# ArduinoNano_LearningBot_4-21-18.net
KiCad netlist of a schematic drawn in EAGLE
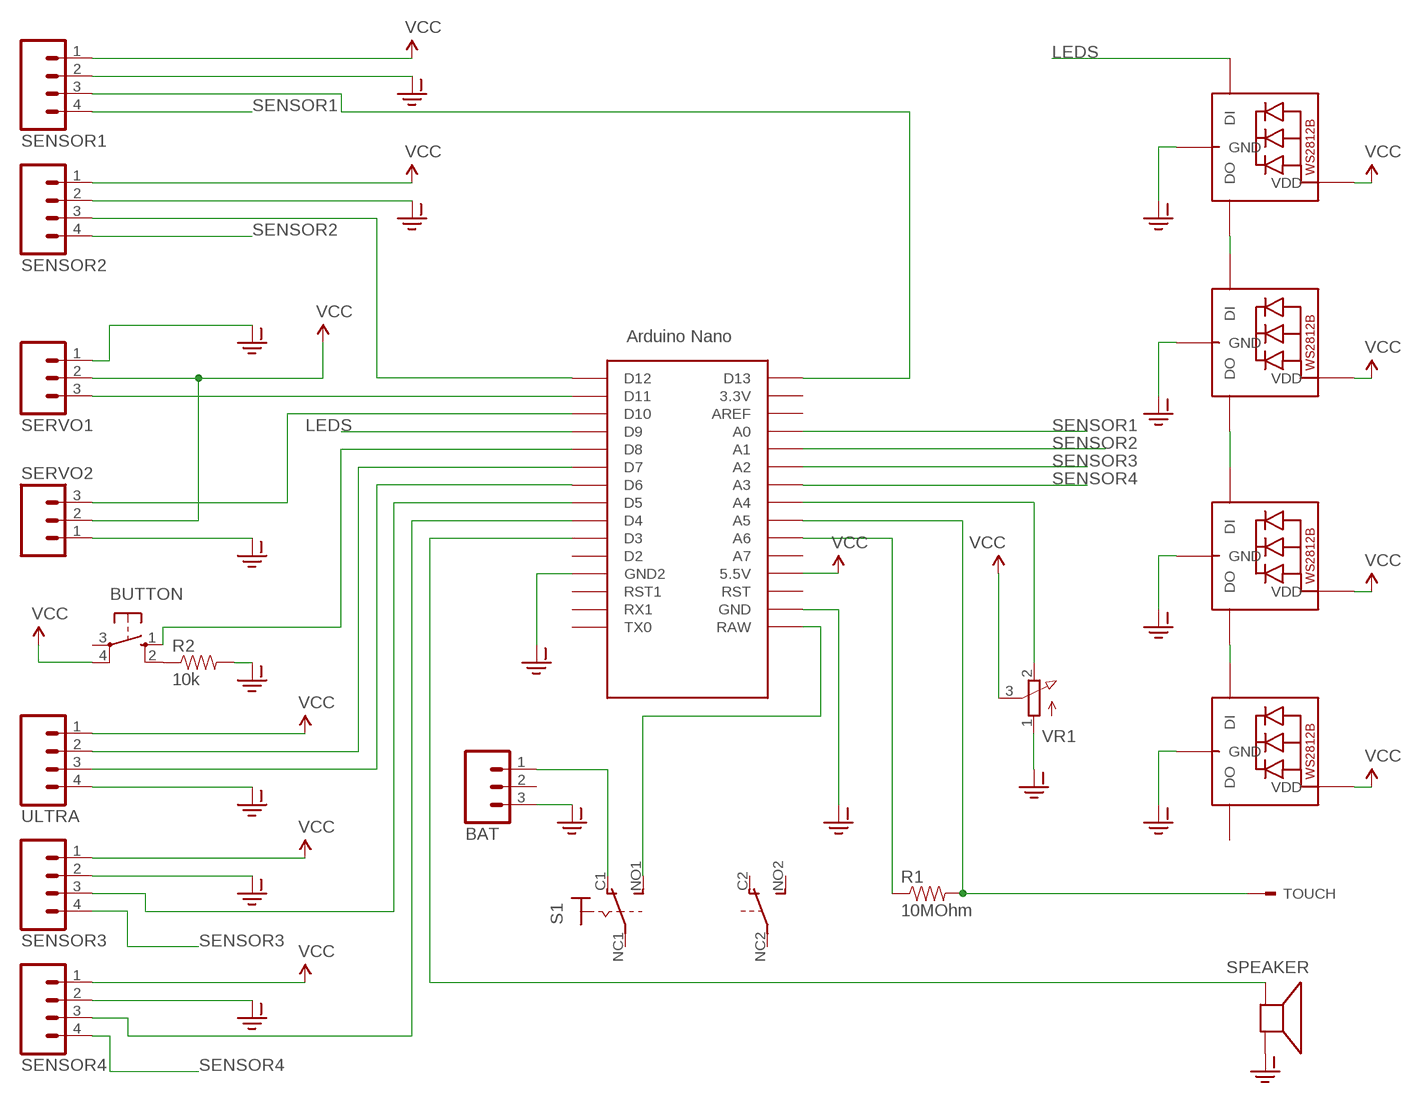
[diagram p0: schematic, sheet 1]

(export (version "E")
  (design (tool "Eeschema 10.0.6"))
  (components
    (comp (ref "BAT")
      (value "M03POLAR")
      (footprint "eagle-import:MOLEX-1X3")
      (libsource (lib "eagle-import") (part "M03POLAR"))
    )
    (comp (ref "BUTTON")
      (value "10-XX")
      (footprint "eagle-import:B3F-10XX")
      (fields (field (name "MPN") "B3F-1000"))
      (libsource (lib "eagle-import") (part "10-XX"))
    )
    (comp (ref "LED1")
      (value "WS2812B5050")
      (footprint "eagle-import:WS2812B")
      (libsource (lib "eagle-import") (part "WS2812B5050"))
    )
    (comp (ref "LED2")
      (value "WS2812B5050")
      (footprint "eagle-import:WS2812B")
      (libsource (lib "eagle-import") (part "WS2812B5050"))
    )
    (comp (ref "LED3")
      (value "WS2812B5050")
      (footprint "eagle-import:WS2812B")
      (libsource (lib "eagle-import") (part "WS2812B5050"))
    )
    (comp (ref "LED4")
      (value "WS2812B5050")
      (footprint "eagle-import:WS2812B")
      (libsource (lib "eagle-import") (part "WS2812B5050"))
    )
    (comp (ref "R1")
      (value "10MOhm")
      (footprint "eagle-import:AXIAL-0.4")
      (libsource (lib "eagle-import") (part "RESISTORPTH-1/4W"))
    )
    (comp (ref "R2")
      (value "10k")
      (footprint "eagle-import:AXIAL-0.4")
      (libsource (lib "eagle-import") (part "RESISTORPTH-1/4W"))
    )
    (comp (ref "S1")
      (value "SWITCH_320-938")
      (footprint "eagle-import:PS22F03")
      (libsource (lib "eagle-import") (part "SWITCH_320-938"))
    )
    (comp (ref "SENSOR1")
      (value "M04LOCK")
      (footprint "eagle-import:1X04_LOCK")
      (libsource (lib "eagle-import") (part "M04LOCK"))
    )
    (comp (ref "SENSOR2")
      (value "M04LOCK")
      (footprint "eagle-import:1X04_LOCK")
      (libsource (lib "eagle-import") (part "M04LOCK"))
    )
    (comp (ref "SENSOR3")
      (value "M04LOCK")
      (footprint "eagle-import:1X04_LOCK")
      (libsource (lib "eagle-import") (part "M04LOCK"))
    )
    (comp (ref "SENSOR4")
      (value "M04LOCK")
      (footprint "eagle-import:1X04_LOCK")
      (libsource (lib "eagle-import") (part "M04LOCK"))
    )
    (comp (ref "SERVO1")
      (value "M03LOCK")
      (footprint "eagle-import:1X03_LOCK")
      (libsource (lib "eagle-import") (part "SparkFun-Connectors_513_M03LOCK"))
    )
    (comp (ref "SERVO2")
      (value "M03LOCK")
      (footprint "eagle-import:1X03_LOCK")
      (libsource (lib "eagle-import") (part "SparkFun-Connectors_513_M03LOCK"))
    )
    (comp (ref "SPEAKER")
      (value "SPEAKER/AL60P")
      (footprint "eagle-import:AL60P")
      (libsource (lib "eagle-import") (part "SPEAKER/AL60P"))
    )
    (comp (ref "TOUCH")
      (value "TOUCHSENSOR")
      (footprint "eagle-import:TOUCH1")
      (libsource (lib "eagle-import") (part "TOUCHSENSOR"))
    )
    (comp (ref "U$1")
      (value "ARDUINO-CLONE_NANO")
      (footprint "eagle-import:ARDUINO-CLONE_NANO")
      (libsource (lib "eagle-import") (part "ARDUINO-CLONE_NANO"))
    )
    (comp (ref "ULTRA")
      (value "M04LOCK")
      (footprint "eagle-import:1X04_LOCK")
      (libsource (lib "eagle-import") (part "M04LOCK"))
    )
    (comp (ref "VR1")
      (value "3RP/1610N-VERTICAL")
      (footprint "eagle-import:3RP_1610N-VERTICAL")
      (libsource (lib "eagle-import") (part "3RP/1610N-VERTICAL"))
    )
  )
  (nets
    (net (code "1") (name "/LEDS") (class "Default")
      (node (ref "LED1") (pin "4-DIN") (pinfunction "DI_4-DIN") (pintype "input"))
      (node (ref "U$1") (pin "D9") (pinfunction "D9_D9") (pintype "bidirectional"))
    )
    (net (code "2") (name "/SENSOR1") (class "Default")
      (node (ref "SENSOR1") (pin "4") (pinfunction "4_4") (pintype "passive"))
      (node (ref "U$1") (pin "A0") (pinfunction "A0_A0") (pintype "bidirectional"))
    )
    (net (code "3") (name "/SENSOR2") (class "Default")
      (node (ref "SENSOR2") (pin "4") (pinfunction "4_4") (pintype "passive"))
      (node (ref "U$1") (pin "A1") (pinfunction "A1_A1") (pintype "bidirectional"))
    )
    (net (code "4") (name "/SENSOR3") (class "Default")
      (node (ref "SENSOR3") (pin "4") (pinfunction "4_4") (pintype "passive"))
      (node (ref "U$1") (pin "A2") (pinfunction "A2_A2") (pintype "bidirectional"))
    )
    (net (code "5") (name "/SENSOR4") (class "Default")
      (node (ref "SENSOR4") (pin "4") (pinfunction "4_4") (pintype "passive"))
      (node (ref "U$1") (pin "A3") (pinfunction "A3_A3") (pintype "bidirectional"))
    )
    (net (code "6") (name "GND-ISO") (class "Default")
      (node (ref "BAT") (pin "3") (pinfunction "3_3") (pintype "passive"))
      (node (ref "LED1") (pin "3-GND") (pinfunction "GND_3-GND") (pintype "power_in"))
      (node (ref "LED2") (pin "3-GND") (pinfunction "GND_3-GND") (pintype "power_in"))
      (node (ref "LED3") (pin "3-GND") (pinfunction "GND_3-GND") (pintype "power_in"))
      (node (ref "LED4") (pin "3-GND") (pinfunction "GND_3-GND") (pintype "power_in"))
      (node (ref "R2") (pin "P$2") (pinfunction "2_P$2") (pintype "passive"))
      (node (ref "SENSOR1") (pin "2") (pinfunction "2_2") (pintype "passive"))
      (node (ref "SENSOR2") (pin "2") (pinfunction "2_2") (pintype "passive"))
      (node (ref "SENSOR3") (pin "2") (pinfunction "2_2") (pintype "passive"))
      (node (ref "SENSOR4") (pin "2") (pinfunction "2_2") (pintype "passive"))
      (node (ref "SERVO1") (pin "1") (pinfunction "1_1") (pintype "passive"))
      (node (ref "SERVO2") (pin "1") (pinfunction "1_1") (pintype "passive"))
      (node (ref "SPEAKER") (pin "1") (pinfunction "+_1") (pintype "passive"))
      (node (ref "U$1") (pin "GND") (pinfunction "GND_GND") (pintype "bidirectional"))
      (node (ref "U$1") (pin "GND1") (pinfunction "GND2_GND1") (pintype "bidirectional"))
      (node (ref "ULTRA") (pin "4") (pinfunction "4_4") (pintype "passive"))
      (node (ref "VR1") (pin "1") (pinfunction "A_1") (pintype "passive"))
    )
    (net (code "7") (name "Net-(BUTTON-S)") (class "Default")
      (node (ref "BUTTON") (pin "1") (pinfunction "S_1") (pintype "passive"))
      (node (ref "U$1") (pin "D8") (pinfunction "D8_D8") (pintype "bidirectional"))
    )
    (net (code "8") (name "Net-(BUTTON-S1)") (class "Default")
      (node (ref "BUTTON") (pin "2") (pinfunction "S1_2") (pintype "passive"))
      (node (ref "R2") (pin "P$1") (pinfunction "1_P$1") (pintype "passive"))
    )
    (net (code "9") (name "Net-(LED1-DO)") (class "Default")
      (node (ref "LED1") (pin "2-DOUT") (pinfunction "DO_2-DOUT") (pintype "output"))
      (node (ref "LED2") (pin "4-DIN") (pinfunction "DI_4-DIN") (pintype "input"))
    )
    (net (code "10") (name "Net-(LED2-DO)") (class "Default")
      (node (ref "LED2") (pin "2-DOUT") (pinfunction "DO_2-DOUT") (pintype "output"))
      (node (ref "LED3") (pin "4-DIN") (pinfunction "DI_4-DIN") (pintype "input"))
    )
    (net (code "11") (name "Net-(LED3-DO)") (class "Default")
      (node (ref "LED3") (pin "2-DOUT") (pinfunction "DO_2-DOUT") (pintype "output"))
      (node (ref "LED4") (pin "4-DIN") (pinfunction "DI_4-DIN") (pintype "input"))
    )
    (net (code "12") (name "Net-(R1-1)") (class "Default")
      (node (ref "R1") (pin "P$1") (pinfunction "1_P$1") (pintype "passive"))
      (node (ref "U$1") (pin "A6") (pinfunction "A6_A6") (pintype "bidirectional"))
    )
    (net (code "13") (name "Net-(R1-2)") (class "Default")
      (node (ref "R1") (pin "P$2") (pinfunction "2_P$2") (pintype "passive"))
      (node (ref "TOUCH") (pin "P$1") (pinfunction "1_P$1") (pintype "passive"))
      (node (ref "U$1") (pin "A5") (pinfunction "A5_A5") (pintype "bidirectional"))
    )
    (net (code "14") (name "Net-(S1A-O)") (class "Default")
      (node (ref "BAT") (pin "1") (pinfunction "1_1") (pintype "passive"))
      (node (ref "S1") (pin "C1") (pinfunction "O_C1") (pintype "passive"))
    )
    (net (code "15") (name "Net-(S1A-S)") (class "Default")
      (node (ref "S1") (pin "NO1") (pinfunction "S_NO1") (pintype "passive"))
      (node (ref "U$1") (pin "RAW") (pinfunction "RAW_RAW") (pintype "bidirectional"))
    )
    (net (code "16") (name "Net-(SENSOR1-Pad3)") (class "Default")
      (node (ref "SENSOR1") (pin "3") (pinfunction "3_3") (pintype "passive"))
      (node (ref "U$1") (pin "D13") (pinfunction "D13_D13") (pintype "bidirectional"))
    )
    (net (code "17") (name "Net-(SENSOR2-Pad3)") (class "Default")
      (node (ref "SENSOR2") (pin "3") (pinfunction "3_3") (pintype "passive"))
      (node (ref "U$1") (pin "D12") (pinfunction "D12_D12") (pintype "bidirectional"))
    )
    (net (code "18") (name "Net-(SENSOR3-Pad3)") (class "Default")
      (node (ref "SENSOR3") (pin "3") (pinfunction "3_3") (pintype "passive"))
      (node (ref "U$1") (pin "D5") (pinfunction "D5_D5") (pintype "bidirectional"))
    )
    (net (code "19") (name "Net-(SENSOR4-Pad3)") (class "Default")
      (node (ref "SENSOR4") (pin "3") (pinfunction "3_3") (pintype "passive"))
      (node (ref "U$1") (pin "D4") (pinfunction "D4_D4") (pintype "bidirectional"))
    )
    (net (code "20") (name "Net-(SERVO1-Pad3)") (class "Default")
      (node (ref "SERVO1") (pin "3") (pinfunction "3_3") (pintype "passive"))
      (node (ref "U$1") (pin "D11") (pinfunction "D11_D11") (pintype "bidirectional"))
    )
    (net (code "21") (name "Net-(SERVO2-Pad3)") (class "Default")
      (node (ref "SERVO2") (pin "3") (pinfunction "3_3") (pintype "passive"))
      (node (ref "U$1") (pin "D10") (pinfunction "D10_D10") (pintype "bidirectional"))
    )
    (net (code "22") (name "Net-(SPEAKER--)") (class "Default")
      (node (ref "SPEAKER") (pin "2") (pinfunction "-_2") (pintype "passive"))
      (node (ref "U$1") (pin "D3") (pinfunction "D3_D3") (pintype "bidirectional"))
    )
    (net (code "23") (name "Net-(U$1-PadD6)") (class "Default")
      (node (ref "U$1") (pin "D6") (pinfunction "D6_D6") (pintype "bidirectional"))
      (node (ref "ULTRA") (pin "3") (pinfunction "3_3") (pintype "passive"))
    )
    (net (code "24") (name "Net-(U$1-PadD7)") (class "Default")
      (node (ref "U$1") (pin "D7") (pinfunction "D7_D7") (pintype "bidirectional"))
      (node (ref "ULTRA") (pin "2") (pinfunction "2_2") (pintype "passive"))
    )
    (net (code "25") (name "Net-(VR1-E)") (class "Default")
      (node (ref "U$1") (pin "A4") (pinfunction "A4_A4") (pintype "bidirectional"))
      (node (ref "VR1") (pin "2") (pinfunction "E_2") (pintype "passive"))
    )
    (net (code "26") (name "VCC") (class "Default")
      (node (ref "BUTTON") (pin "4") (pinfunction "P1_4") (pintype "passive"))
      (node (ref "LED1") (pin "1-VDD") (pinfunction "VDD_1-VDD") (pintype "power_in"))
      (node (ref "LED2") (pin "1-VDD") (pinfunction "VDD_1-VDD") (pintype "power_in"))
      (node (ref "LED3") (pin "1-VDD") (pinfunction "VDD_1-VDD") (pintype "power_in"))
      (node (ref "LED4") (pin "1-VDD") (pinfunction "VDD_1-VDD") (pintype "power_in"))
      (node (ref "SENSOR1") (pin "1") (pinfunction "1_1") (pintype "passive"))
      (node (ref "SENSOR2") (pin "1") (pinfunction "1_1") (pintype "passive"))
      (node (ref "SENSOR3") (pin "1") (pinfunction "1_1") (pintype "passive"))
      (node (ref "SENSOR4") (pin "1") (pinfunction "1_1") (pintype "passive"))
      (node (ref "SERVO1") (pin "2") (pinfunction "2_2") (pintype "passive"))
      (node (ref "SERVO2") (pin "2") (pinfunction "2_2") (pintype "passive"))
      (node (ref "U$1") (pin "5V") (pinfunction "5.5V_5V") (pintype "bidirectional"))
      (node (ref "ULTRA") (pin "1") (pinfunction "1_1") (pintype "passive"))
      (node (ref "VR1") (pin "3") (pinfunction "S_3") (pintype "passive"))
    )
    (net (code "27") (name "unconnected-(BAT-Pad2)") (class "Default")
      (node (ref "BAT") (pin "2") (pinfunction "2_2") (pintype "passive"))
    )
    (net (code "28") (name "unconnected-(BUTTON-P-Pad3)") (class "Default")
      (node (ref "BUTTON") (pin "3") (pinfunction "P_3") (pintype "passive"))
    )
    (net (code "29") (name "unconnected-(LED4-DO-Pad2-DOUT)") (class "Default")
      (node (ref "LED4") (pin "2-DOUT") (pinfunction "DO_2-DOUT") (pintype "output"))
    )
    (net (code "30") (name "unconnected-(S1A-P-PadNC1)") (class "Default")
      (node (ref "S1") (pin "NC1") (pinfunction "P_NC1") (pintype "passive"))
    )
    (net (code "31") (name "unconnected-(S1B-O-PadC2)") (class "Default")
      (node (ref "S1") (pin "C2") (pinfunction "O_C2") (pintype "passive"))
    )
    (net (code "32") (name "unconnected-(S1B-P-PadNC2)") (class "Default")
      (node (ref "S1") (pin "NC2") (pinfunction "P_NC2") (pintype "passive"))
    )
    (net (code "33") (name "unconnected-(S1B-S-PadNO2)") (class "Default")
      (node (ref "S1") (pin "NO2") (pinfunction "S_NO2") (pintype "passive"))
    )
    (net (code "34") (name "unconnected-(U$1-Pad3.3V)") (class "Default")
      (node (ref "U$1") (pin "3.3V") (pinfunction "3.3V_3.3V") (pintype "bidirectional"))
    )
    (net (code "35") (name "unconnected-(U$1-PadA7)") (class "Default")
      (node (ref "U$1") (pin "A7") (pinfunction "A7_A7") (pintype "bidirectional"))
    )
    (net (code "36") (name "unconnected-(U$1-PadAREF)") (class "Default")
      (node (ref "U$1") (pin "AREF") (pinfunction "AREF_AREF") (pintype "bidirectional"))
    )
    (net (code "37") (name "unconnected-(U$1-PadD2)") (class "Default")
      (node (ref "U$1") (pin "D2") (pinfunction "D2_D2") (pintype "bidirectional"))
    )
    (net (code "38") (name "unconnected-(U$1-PadRST)") (class "Default")
      (node (ref "U$1") (pin "RST") (pinfunction "RST_RST") (pintype "bidirectional"))
    )
    (net (code "39") (name "unconnected-(U$1-PadRST1)") (class "Default")
      (node (ref "U$1") (pin "RST1") (pinfunction "RST1_RST1") (pintype "bidirectional"))
    )
    (net (code "40") (name "unconnected-(U$1-PadRX1)") (class "Default")
      (node (ref "U$1") (pin "RX1") (pinfunction "RX1_RX1") (pintype "bidirectional"))
    )
    (net (code "41") (name "unconnected-(U$1-PadTX0)") (class "Default")
      (node (ref "U$1") (pin "TX0") (pinfunction "TX0_TX0") (pintype "bidirectional"))
    )
  )
)
